# main.net
KiCad netlist of a schematic drawn in EAGLE
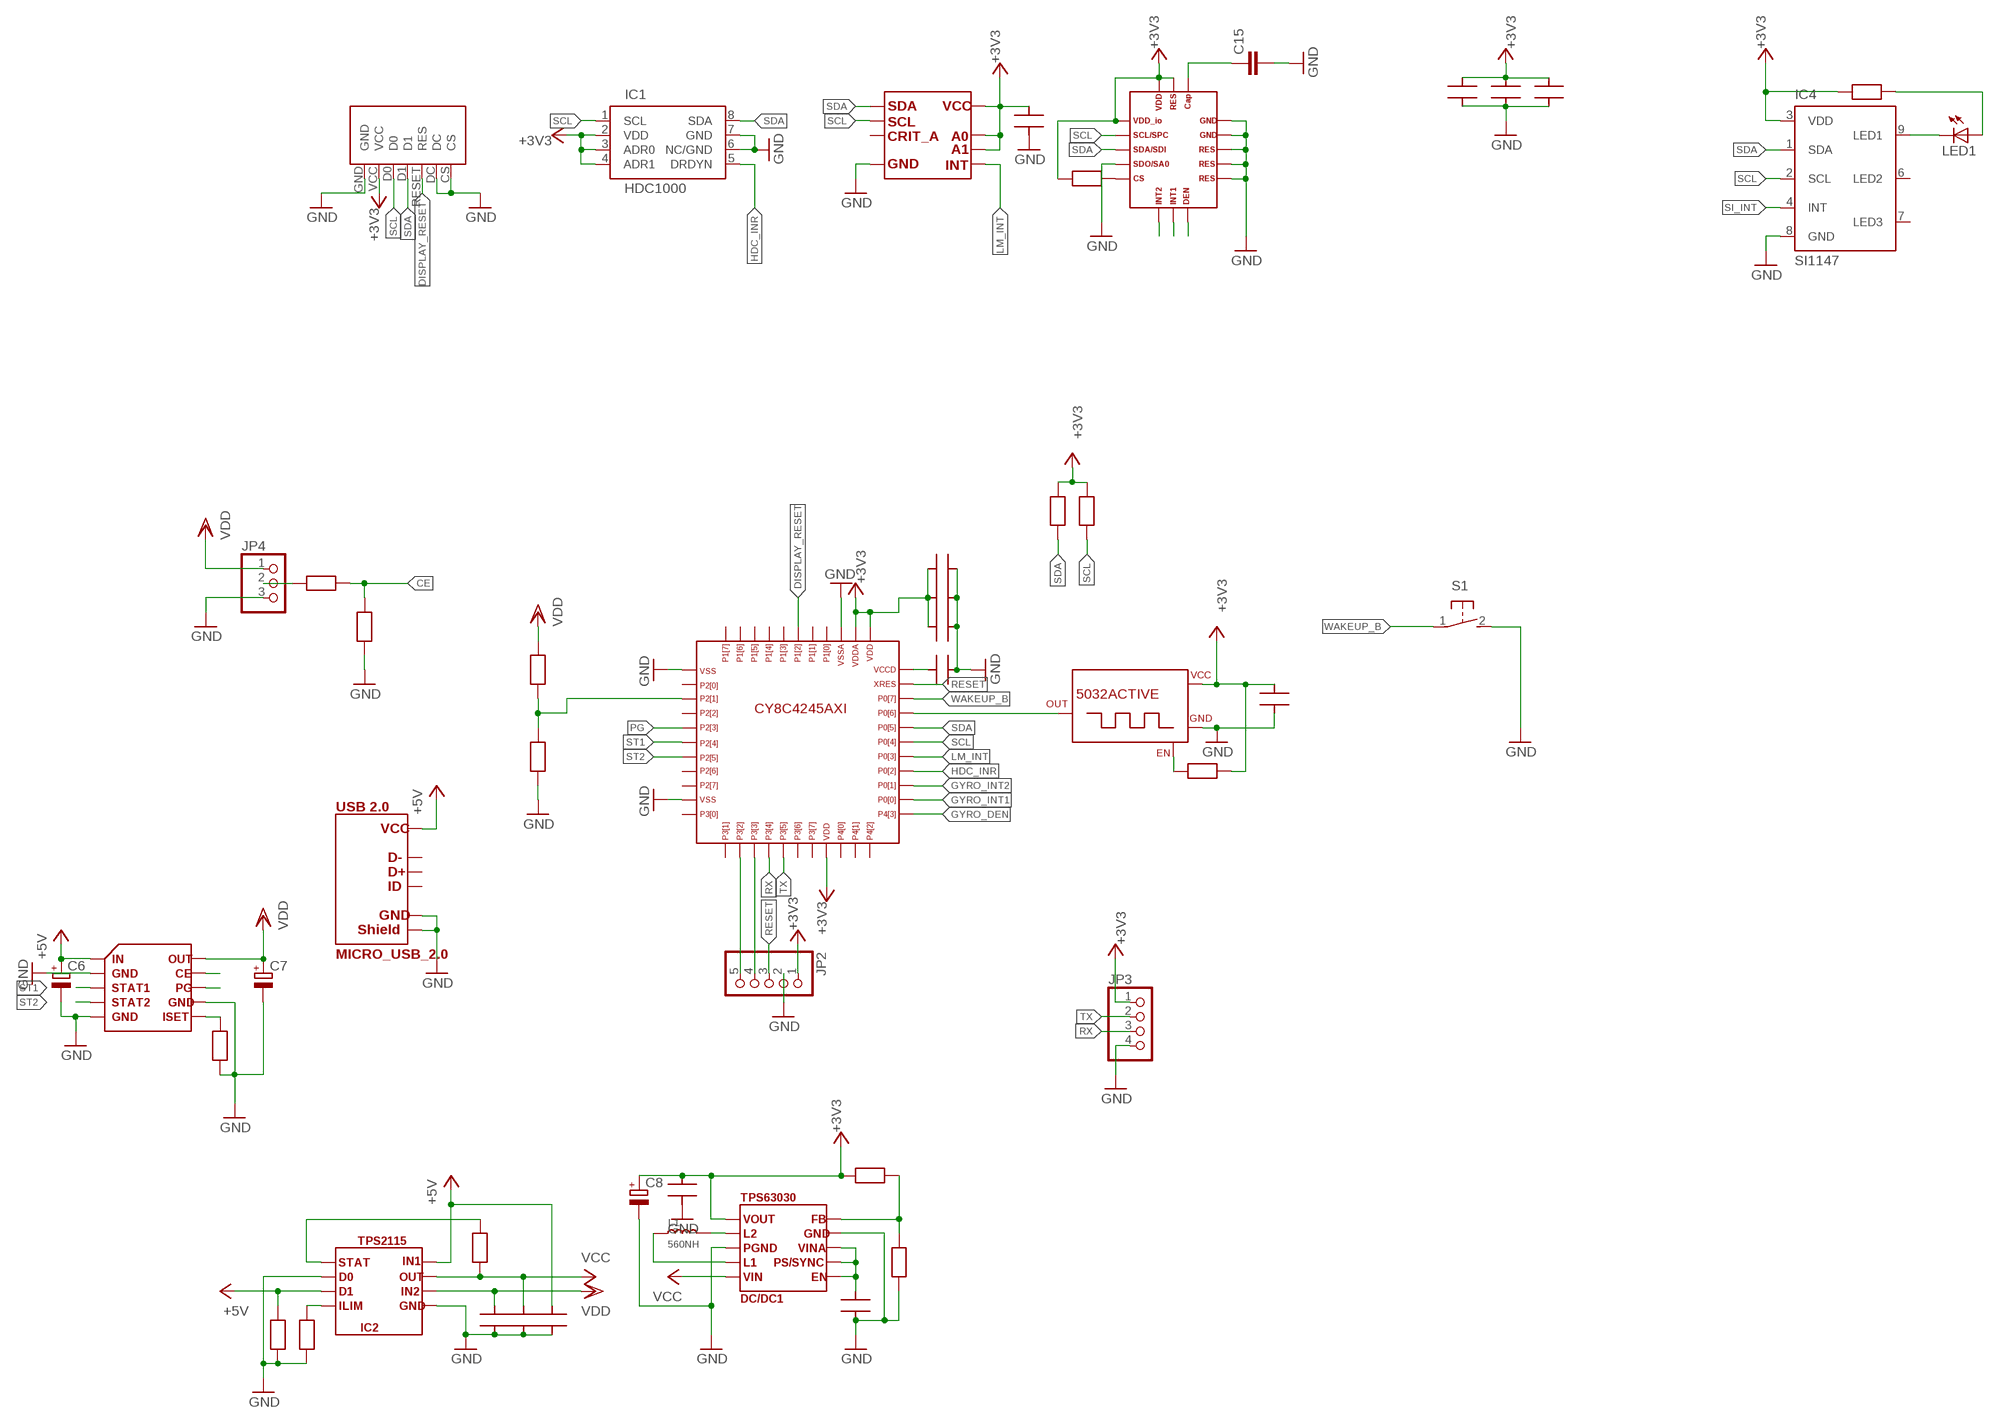
[diagram p0: schematic, sheet 1]

(export (version "E")
  (design (tool "Eeschema 10.0.6"))
  (components
    (comp (ref "C1")
      (value "CAP0603")
      (footprint "eagle-import:C0603")
      (libsource (lib "eagle-import") (part "CAP0603"))
    )
    (comp (ref "C2")
      (value "CAP0603")
      (footprint "eagle-import:C0603")
      (libsource (lib "eagle-import") (part "CAP0603"))
    )
    (comp (ref "C3")
      (value "CAP0603")
      (footprint "eagle-import:C0603")
      (libsource (lib "eagle-import") (part "CAP0603"))
    )
    (comp (ref "C4")
      (value "CAP0603")
      (footprint "eagle-import:C0603")
      (libsource (lib "eagle-import") (part "CAP0603"))
    )
    (comp (ref "C5")
      (value "CAP0603")
      (footprint "eagle-import:C0603")
      (libsource (lib "eagle-import") (part "CAP0603"))
    )
    (comp (ref "C6")
      (value "CPOL-EUSMCA")
      (footprint "eagle-import:SMC_A")
      (libsource (lib "eagle-import") (part "CPOL-EUSMCA"))
    )
    (comp (ref "C7")
      (value "CPOL-EUSMCA")
      (footprint "eagle-import:SMC_A")
      (libsource (lib "eagle-import") (part "CPOL-EUSMCA"))
    )
    (comp (ref "C8")
      (value "CPOL-EUSMCA")
      (footprint "eagle-import:SMC_A")
      (libsource (lib "eagle-import") (part "CPOL-EUSMCA"))
    )
    (comp (ref "C9")
      (value "CAP0603")
      (footprint "eagle-import:C0603")
      (libsource (lib "eagle-import") (part "CAP0603"))
    )
    (comp (ref "C10")
      (value "CAP0603")
      (footprint "eagle-import:C0603")
      (libsource (lib "eagle-import") (part "CAP0603"))
    )
    (comp (ref "C11")
      (value "CAP0603")
      (footprint "eagle-import:C0603")
      (libsource (lib "eagle-import") (part "CAP0603"))
    )
    (comp (ref "C12")
      (value "CAP0603")
      (footprint "eagle-import:C0603")
      (libsource (lib "eagle-import") (part "CAP0603"))
    )
    (comp (ref "C13")
      (value "CAP0603")
      (footprint "eagle-import:C0603")
      (libsource (lib "eagle-import") (part "CAP0603"))
    )
    (comp (ref "C14")
      (value "CAP0603")
      (footprint "eagle-import:C0603")
      (libsource (lib "eagle-import") (part "CAP0603"))
    )
    (comp (ref "C15")
      (value "C-EUC1206")
      (footprint "eagle-import:C1206")
      (libsource (lib "eagle-import") (part "C-EUC1206"))
    )
    (comp (ref "C18")
      (value "CAP0603")
      (footprint "eagle-import:C0603")
      (libsource (lib "eagle-import") (part "CAP0603"))
    )
    (comp (ref "C19")
      (value "CAP0603")
      (footprint "eagle-import:C0603")
      (libsource (lib "eagle-import") (part "CAP0603"))
    )
    (comp (ref "C20")
      (value "CAP0603")
      (footprint "eagle-import:C0603")
      (libsource (lib "eagle-import") (part "CAP0603"))
    )
    (comp (ref "DC/DC1")
      (value "TPS63030")
      (footprint "eagle-import:WSON10")
      (libsource (lib "eagle-import") (part "TPS63030"))
    )
    (comp (ref "DIS1")
      (value "ER-OLED_BREACKOUT")
      (footprint "eagle-import:ER-OLED_BRECKOUT")
      (libsource (lib "eagle-import") (part "ER-OLED_BREACKOUT"))
    )
    (comp (ref "GYRO1")
      (value "L3GD20H")
      (footprint "eagle-import:LGA_3X3_16")
      (libsource (lib "eagle-import") (part "L3GD20H"))
    )
    (comp (ref "IC1")
      (value "HDC1000")
      (footprint "eagle-import:DSBGA-8")
      (libsource (lib "eagle-import") (part "HDC1000"))
    )
    (comp (ref "IC2")
      (value "TPS2115")
      (footprint "eagle-import:TSSOP8")
      (libsource (lib "eagle-import") (part "TPS2115"))
    )
    (comp (ref "IC3")
      (value "BQ24080-Q1,")
      (footprint "eagle-import:VSON10")
      (libsource (lib "eagle-import") (part "BQ24080-Q1,"))
    )
    (comp (ref "IC4")
      (value "SI1147")
      (footprint "eagle-import:QFN-10")
      (libsource (lib "eagle-import") (part "SI1147"))
    )
    (comp (ref "JP2")
      (value "PINHD-1X5")
      (footprint "eagle-import:1X05")
      (libsource (lib "eagle-import") (part "PINHD-1X5"))
    )
    (comp (ref "JP3")
      (value "PINHD-1X4")
      (footprint "eagle-import:1X04")
      (libsource (lib "eagle-import") (part "PINHD-1X4"))
    )
    (comp (ref "JP4")
      (value "PINHD-1X3")
      (footprint "eagle-import:1X03")
      (libsource (lib "eagle-import") (part "PINHD-1X3"))
    )
    (comp (ref "L1")
      (value "560NH")
      (footprint "eagle-import:L0805")
      (libsource (lib "eagle-import") (part "SMD-INDUCTOR-560NH-10%(0805)"))
    )
    (comp (ref "LED1")
      (value "LED3MM")
      (footprint "eagle-import:LED3MM")
      (libsource (lib "eagle-import") (part "LED3MM"))
    )
    (comp (ref "R1")
      (value "RES0603")
      (footprint "eagle-import:R0603")
      (libsource (lib "eagle-import") (part "RES0603"))
    )
    (comp (ref "R2")
      (value "RES0603")
      (footprint "eagle-import:R0603")
      (libsource (lib "eagle-import") (part "RES0603"))
    )
    (comp (ref "R3")
      (value "RES0603")
      (footprint "eagle-import:R0603")
      (libsource (lib "eagle-import") (part "RES0603"))
    )
    (comp (ref "R4")
      (value "RES0603")
      (footprint "eagle-import:R0603")
      (libsource (lib "eagle-import") (part "RES0603"))
    )
    (comp (ref "R5")
      (value "RES0603")
      (footprint "eagle-import:R0603")
      (libsource (lib "eagle-import") (part "RES0603"))
    )
    (comp (ref "R6")
      (value "RES0603")
      (footprint "eagle-import:R0603")
      (libsource (lib "eagle-import") (part "RES0603"))
    )
    (comp (ref "R7")
      (value "RES0603")
      (footprint "eagle-import:R0603")
      (libsource (lib "eagle-import") (part "RES0603"))
    )
    (comp (ref "R8")
      (value "RES0603")
      (footprint "eagle-import:R0603")
      (libsource (lib "eagle-import") (part "RES0603"))
    )
    (comp (ref "R9")
      (value "RES0603")
      (footprint "eagle-import:R0603")
      (libsource (lib "eagle-import") (part "RES0603"))
    )
    (comp (ref "R10")
      (value "RES0603")
      (footprint "eagle-import:R0603")
      (libsource (lib "eagle-import") (part "RES0603"))
    )
    (comp (ref "R11")
      (value "RES0603")
      (footprint "eagle-import:R0603")
      (libsource (lib "eagle-import") (part "RES0603"))
    )
    (comp (ref "R12")
      (value "RES0603")
      (footprint "eagle-import:R0603")
      (libsource (lib "eagle-import") (part "RES0603"))
    )
    (comp (ref "R13")
      (value "RES0603")
      (footprint "eagle-import:R0603")
      (libsource (lib "eagle-import") (part "RES0603"))
    )
    (comp (ref "R14")
      (value "RES0603")
      (footprint "eagle-import:R0603")
      (libsource (lib "eagle-import") (part "RES0603"))
    )
    (comp (ref "R15")
      (value "RES0603")
      (footprint "eagle-import:R0603")
      (libsource (lib "eagle-import") (part "RES0603"))
    )
    (comp (ref "S1")
      (value "31-XX")
      (footprint "eagle-import:B3F-31XX")
      (fields (field (name "MPN") "B3F-3100"))
      (libsource (lib "eagle-import") (part "31-XX"))
    )
    (comp (ref "TMP1")
      (value "LM92")
      (footprint "eagle-import:SOIC8-1.27-5X4MM")
      (libsource (lib "eagle-import") (part "LM92"))
    )
    (comp (ref "U$1")
      (value "CY8C4245")
      (footprint "eagle-import:TQFP44_CY_LOGO")
      (libsource (lib "eagle-import") (part "CY8C4245"))
    )
    (comp (ref "U$2")
      (value "5032ACTIVE")
      (footprint "eagle-import:5030A")
      (libsource (lib "eagle-import") (part "5032ACTIVE"))
    )
    (comp (ref "USB_CON1")
      (value "MICRO_USB_2.0")
      (footprint "eagle-import:MICRO-USB5+4P-SMD-0.65")
      (libsource (lib "eagle-import") (part "MICRO_USB_2.0"))
    )
  )
  (nets
    (net (code "1") (name "+3V3") (class "Default")
      (node (ref "C10") (pin "2") (pinfunction "P$2_2") (pintype "bidirectional"))
      (node (ref "C11") (pin "2") (pinfunction "P$2_2") (pintype "bidirectional"))
      (node (ref "C12") (pin "2") (pinfunction "P$2_2") (pintype "bidirectional"))
      (node (ref "C13") (pin "1") (pinfunction "P$1_1") (pintype "bidirectional"))
      (node (ref "C14") (pin "1") (pinfunction "P$1_1") (pintype "bidirectional"))
      (node (ref "C18") (pin "1") (pinfunction "P$1_1") (pintype "bidirectional"))
      (node (ref "C19") (pin "1") (pinfunction "P$1_1") (pintype "bidirectional"))
      (node (ref "C20") (pin "1") (pinfunction "P$1_1") (pintype "bidirectional"))
      (node (ref "C5") (pin "2") (pinfunction "P$2_2") (pintype "bidirectional"))
      (node (ref "C8") (pin "+") (pinfunction "+_+") (pintype "passive"))
      (node (ref "DC/DC1") (pin "P$1") (pinfunction "P$1_P$1") (pintype "bidirectional"))
      (node (ref "DIS1") (pin "VCC") (pinfunction "VCC_VCC") (pintype "bidirectional"))
      (node (ref "GYRO1") (pin "1") (pinfunction "P$1_1") (pintype "bidirectional"))
      (node (ref "GYRO1") (pin "15") (pinfunction "P$15_15") (pintype "bidirectional"))
      (node (ref "GYRO1") (pin "16") (pinfunction "P$16_16") (pintype "bidirectional"))
      (node (ref "IC1") (pin "2") (pinfunction "VDD_2") (pintype "power_in"))
      (node (ref "IC1") (pin "3") (pinfunction "ADR0_3") (pintype "bidirectional"))
      (node (ref "IC1") (pin "4") (pinfunction "ADR1_4") (pintype "bidirectional"))
      (node (ref "IC4") (pin "3") (pinfunction "VDD_3") (pintype "power_in"))
      (node (ref "JP2") (pin "1") (pinfunction "1_1") (pintype "passive"))
      (node (ref "JP3") (pin "1") (pinfunction "1_1") (pintype "passive"))
      (node (ref "R10") (pin "2") (pinfunction "P$2_2") (pintype "bidirectional"))
      (node (ref "R11") (pin "1") (pinfunction "P$1_1") (pintype "bidirectional"))
      (node (ref "R12") (pin "2") (pinfunction "P$2_2") (pintype "bidirectional"))
      (node (ref "R13") (pin "2") (pinfunction "P$2_2") (pintype "bidirectional"))
      (node (ref "R5") (pin "1") (pinfunction "P$1_1") (pintype "bidirectional"))
      (node (ref "R9") (pin "2") (pinfunction "P$2_2") (pintype "bidirectional"))
      (node (ref "TMP1") (pin "6") (pinfunction "OUT_6") (pintype "bidirectional"))
      (node (ref "TMP1") (pin "7") (pinfunction "OUT_7") (pintype "bidirectional"))
      (node (ref "TMP1") (pin "8") (pinfunction "OUT_8") (pintype "bidirectional"))
      (node (ref "U$1") (pin "19") (pinfunction "19_19") (pintype "bidirectional"))
      (node (ref "U$1") (pin "34") (pinfunction "34_34") (pintype "bidirectional"))
      (node (ref "U$1") (pin "35") (pinfunction "35_35") (pintype "bidirectional"))
      (node (ref "U$2") (pin "4") (pinfunction "+5V_4") (pintype "bidirectional"))
    )
    (net (code "2") (name "+5V") (class "Default")
      (node (ref "C3") (pin "2") (pinfunction "P$2_2") (pintype "bidirectional"))
      (node (ref "C6") (pin "+") (pinfunction "+_+") (pintype "passive"))
      (node (ref "IC2") (pin "P$3") (pinfunction "P$3_P$3") (pintype "bidirectional"))
      (node (ref "IC2") (pin "P$8") (pinfunction "P$8_P$8") (pintype "bidirectional"))
      (node (ref "IC3") (pin "P$1") (pinfunction "P$1_P$1") (pintype "bidirectional"))
      (node (ref "R2") (pin "2") (pinfunction "P$2_2") (pintype "bidirectional"))
      (node (ref "USB_CON1") (pin "1") (pinfunction "P$1_1") (pintype "bidirectional"))
    )
    (net (code "3") (name "CE") (class "Default")
      (node (ref "IC3") (pin "P$9") (pinfunction "P$9_P$9") (pintype "bidirectional"))
      (node (ref "R14") (pin "1") (pinfunction "P$1_1") (pintype "bidirectional"))
      (node (ref "R15") (pin "1") (pinfunction "P$1_1") (pintype "bidirectional"))
    )
    (net (code "4") (name "DISPLAY_RESET") (class "Default")
      (node (ref "DIS1") (pin "RESET") (pinfunction "RES_RESET") (pintype "bidirectional"))
      (node (ref "U$1") (pin "39") (pinfunction "39_39") (pintype "bidirectional"))
    )
    (net (code "5") (name "GND") (class "Default")
      (node (ref "C1") (pin "1") (pinfunction "P$1_1") (pintype "bidirectional"))
      (node (ref "C10") (pin "1") (pinfunction "P$1_1") (pintype "bidirectional"))
      (node (ref "C11") (pin "1") (pinfunction "P$1_1") (pintype "bidirectional"))
      (node (ref "C12") (pin "1") (pinfunction "P$1_1") (pintype "bidirectional"))
      (node (ref "C13") (pin "2") (pinfunction "P$2_2") (pintype "bidirectional"))
      (node (ref "C14") (pin "2") (pinfunction "P$2_2") (pintype "bidirectional"))
      (node (ref "C15") (pin "2") (pinfunction "2_2") (pintype "passive"))
      (node (ref "C18") (pin "2") (pinfunction "P$2_2") (pintype "bidirectional"))
      (node (ref "C19") (pin "2") (pinfunction "P$2_2") (pintype "bidirectional"))
      (node (ref "C2") (pin "1") (pinfunction "P$1_1") (pintype "bidirectional"))
      (node (ref "C20") (pin "2") (pinfunction "P$2_2") (pintype "bidirectional"))
      (node (ref "C3") (pin "1") (pinfunction "P$1_1") (pintype "bidirectional"))
      (node (ref "C4") (pin "1") (pinfunction "P$1_1") (pintype "bidirectional"))
      (node (ref "C5") (pin "1") (pinfunction "P$1_1") (pintype "bidirectional"))
      (node (ref "C6") (pin "-") (pinfunction "-_-") (pintype "passive"))
      (node (ref "C7") (pin "-") (pinfunction "-_-") (pintype "passive"))
      (node (ref "C8") (pin "-") (pinfunction "-_-") (pintype "passive"))
      (node (ref "C9") (pin "1") (pinfunction "P$1_1") (pintype "bidirectional"))
      (node (ref "DC/DC1") (pin "EPAD_B") (pinfunction "P$3_EPAD_B") (pintype "bidirectional"))
      (node (ref "DC/DC1") (pin "EPAD_T") (pinfunction "P$3_EPAD_T") (pintype "bidirectional"))
      (node (ref "DC/DC1") (pin "EPAD_VIA") (pinfunction "P$3_EPAD_VIA") (pintype "bidirectional"))
      (node (ref "DC/DC1") (pin "P$3") (pinfunction "P$3_P$3") (pintype "bidirectional"))
      (node (ref "DC/DC1") (pin "P$9") (pinfunction "P$9_P$9") (pintype "bidirectional"))
      (node (ref "DIS1") (pin "CS") (pinfunction "CS_CS") (pintype "bidirectional"))
      (node (ref "DIS1") (pin "DC") (pinfunction "DC_DC") (pintype "bidirectional"))
      (node (ref "DIS1") (pin "GND") (pinfunction "GND_GND") (pintype "bidirectional"))
      (node (ref "GYRO1") (pin "10") (pinfunction "P$10_10") (pintype "bidirectional"))
      (node (ref "GYRO1") (pin "11") (pinfunction "P$11_11") (pintype "bidirectional"))
      (node (ref "GYRO1") (pin "12") (pinfunction "P$12_12") (pintype "bidirectional"))
      (node (ref "GYRO1") (pin "13") (pinfunction "P$13_13") (pintype "bidirectional"))
      (node (ref "GYRO1") (pin "4") (pinfunction "P$4_4") (pintype "bidirectional"))
      (node (ref "GYRO1") (pin "9") (pinfunction "P$9_9") (pintype "bidirectional"))
      (node (ref "IC1") (pin "6") (pinfunction "NC/GND_6") (pintype "bidirectional"))
      (node (ref "IC1") (pin "7") (pinfunction "GND_7") (pintype "power_in"))
      (node (ref "IC2") (pin "P$2") (pinfunction "P$2_P$2") (pintype "bidirectional"))
      (node (ref "IC2") (pin "P$5") (pinfunction "P$5_P$5") (pintype "bidirectional"))
      (node (ref "IC3") (pin "P$2") (pinfunction "P$2_P$2") (pintype "bidirectional"))
      (node (ref "IC3") (pin "P$5") (pinfunction "P$5_P$5") (pintype "bidirectional"))
      (node (ref "IC3") (pin "P$7") (pinfunction "P$7_P$7") (pintype "bidirectional"))
      (node (ref "IC3") (pin "PAD1") (pinfunction "P$5_PAD1") (pintype "bidirectional"))
      (node (ref "IC3") (pin "PAD2") (pinfunction "P$5_PAD2") (pintype "bidirectional"))
      (node (ref "IC3") (pin "PAD3") (pinfunction "P$5_PAD3") (pintype "bidirectional"))
      (node (ref "IC3") (pin "PAD4") (pinfunction "P$5_PAD4") (pintype "bidirectional"))
      (node (ref "IC3") (pin "PAD5") (pinfunction "P$5_PAD5") (pintype "bidirectional"))
      (node (ref "IC4") (pin "8") (pinfunction "GND_8") (pintype "power_in"))
      (node (ref "JP2") (pin "2") (pinfunction "2_2") (pintype "passive"))
      (node (ref "JP3") (pin "4") (pinfunction "4_4") (pintype "passive"))
      (node (ref "JP4") (pin "3") (pinfunction "3_3") (pintype "passive"))
      (node (ref "R1") (pin "1") (pinfunction "P$1_1") (pintype "bidirectional"))
      (node (ref "R15") (pin "2") (pinfunction "P$2_2") (pintype "bidirectional"))
      (node (ref "R2") (pin "1") (pinfunction "P$1_1") (pintype "bidirectional"))
      (node (ref "R4") (pin "2") (pinfunction "P$2_2") (pintype "bidirectional"))
      (node (ref "R6") (pin "1") (pinfunction "P$1_1") (pintype "bidirectional"))
      (node (ref "R8") (pin "1") (pinfunction "P$1_1") (pintype "bidirectional"))
      (node (ref "S1") (pin "2") (pinfunction "S_2") (pintype "passive"))
      (node (ref "TMP1") (pin "4") (pinfunction "OUT_4") (pintype "bidirectional"))
      (node (ref "U$1") (pin "1") (pinfunction "1_1") (pintype "bidirectional"))
      (node (ref "U$1") (pin "10") (pinfunction "10_10") (pintype "bidirectional"))
      (node (ref "U$1") (pin "36") (pinfunction "36_36") (pintype "bidirectional"))
      (node (ref "U$2") (pin "2") (pinfunction "GND_2") (pintype "bidirectional"))
      (node (ref "USB_CON1") (pin "5") (pinfunction "P$5_5") (pintype "bidirectional"))
      (node (ref "USB_CON1") (pin "P$1") (pinfunction "P$6_P$1") (pintype "bidirectional"))
      (node (ref "USB_CON1") (pin "P$2") (pinfunction "P$6_P$2") (pintype "bidirectional"))
      (node (ref "USB_CON1") (pin "P$3") (pinfunction "P$6_P$3") (pintype "bidirectional"))
      (node (ref "USB_CON1") (pin "P$4") (pinfunction "P$6_P$4") (pintype "bidirectional"))
    )
    (net (code "6") (name "GYRO_DEN") (class "Default")
      (node (ref "GYRO1") (pin "8") (pinfunction "P$8_8") (pintype "bidirectional"))
      (node (ref "U$1") (pin "23") (pinfunction "23_23") (pintype "bidirectional"))
    )
    (net (code "7") (name "GYRO_INT1") (class "Default")
      (node (ref "GYRO1") (pin "7") (pinfunction "P$7_7") (pintype "bidirectional"))
      (node (ref "U$1") (pin "24") (pinfunction "24_24") (pintype "bidirectional"))
    )
    (net (code "8") (name "GYRO_INT2") (class "Default")
      (node (ref "GYRO1") (pin "6") (pinfunction "P$6_6") (pintype "bidirectional"))
      (node (ref "U$1") (pin "25") (pinfunction "25_25") (pintype "bidirectional"))
    )
    (net (code "9") (name "HDC_INR") (class "Default")
      (node (ref "IC1") (pin "5") (pinfunction "DRDYN_5") (pintype "bidirectional"))
      (node (ref "U$1") (pin "26") (pinfunction "26_26") (pintype "bidirectional"))
    )
    (net (code "10") (name "LM_INT") (class "Default")
      (node (ref "TMP1") (pin "5") (pinfunction "OUT_5") (pintype "bidirectional"))
      (node (ref "U$1") (pin "27") (pinfunction "27_27") (pintype "bidirectional"))
    )
    (net (code "11") (name "Net-(C4-P$2)") (class "Default")
      (node (ref "C4") (pin "2") (pinfunction "P$2_2") (pintype "bidirectional"))
      (node (ref "DC/DC1") (pin "P$6") (pinfunction "P$6_P$6") (pintype "bidirectional"))
      (node (ref "DC/DC1") (pin "P$7") (pinfunction "P$7_P$7") (pintype "bidirectional"))
      (node (ref "DC/DC1") (pin "P$8") (pinfunction "P$8_P$8") (pintype "bidirectional"))
    )
    (net (code "12") (name "Net-(C9-P$2)") (class "Default")
      (node (ref "C9") (pin "2") (pinfunction "P$2_2") (pintype "bidirectional"))
      (node (ref "U$1") (pin "33") (pinfunction "33_33") (pintype "bidirectional"))
    )
    (net (code "13") (name "Net-(DC/DC1-PadP$2)") (class "Default")
      (node (ref "DC/DC1") (pin "P$2") (pinfunction "P$2_P$2") (pintype "bidirectional"))
      (node (ref "L1") (pin "2") (pinfunction "2_2") (pintype "passive"))
    )
    (net (code "14") (name "Net-(DC/DC1-PadP$4)") (class "Default")
      (node (ref "DC/DC1") (pin "P$4") (pinfunction "P$4_P$4") (pintype "bidirectional"))
      (node (ref "L1") (pin "1") (pinfunction "1_1") (pintype "passive"))
    )
    (net (code "15") (name "Net-(GYRO1-P$5)") (class "Default")
      (node (ref "GYRO1") (pin "5") (pinfunction "P$5_5") (pintype "bidirectional"))
      (node (ref "R12") (pin "1") (pinfunction "P$1_1") (pintype "bidirectional"))
    )
    (net (code "16") (name "Net-(GYRO1-P$14)") (class "Default")
      (node (ref "C15") (pin "1") (pinfunction "1_1") (pintype "passive"))
      (node (ref "GYRO1") (pin "14") (pinfunction "P$14_14") (pintype "bidirectional"))
    )
    (net (code "17") (name "Net-(IC4-LED1)") (class "Default")
      (node (ref "IC4") (pin "9") (pinfunction "LED1_9") (pintype "output"))
      (node (ref "LED1") (pin "K") (pinfunction "C_K") (pintype "passive"))
    )
    (net (code "18") (name "Net-(JP2-Pad4)") (class "Default")
      (node (ref "JP2") (pin "4") (pinfunction "4_4") (pintype "passive"))
      (node (ref "U$1") (pin "14") (pinfunction "14_14") (pintype "bidirectional"))
    )
    (net (code "19") (name "Net-(JP2-Pad5)") (class "Default")
      (node (ref "JP2") (pin "5") (pinfunction "5_5") (pintype "passive"))
      (node (ref "U$1") (pin "13") (pinfunction "13_13") (pintype "bidirectional"))
    )
    (net (code "20") (name "Net-(R1-P$2)") (class "Default")
      (node (ref "IC2") (pin "P$4") (pinfunction "P$4_P$4") (pintype "bidirectional"))
      (node (ref "R1") (pin "2") (pinfunction "P$2_2") (pintype "bidirectional"))
    )
    (net (code "21") (name "Net-(R3-P$2)") (class "Default")
      (node (ref "IC2") (pin "P$1") (pinfunction "P$1_P$1") (pintype "bidirectional"))
      (node (ref "R3") (pin "2") (pinfunction "P$2_2") (pintype "bidirectional"))
    )
    (net (code "22") (name "Net-(R4-P$1)") (class "Default")
      (node (ref "DC/DC1") (pin "P$10") (pinfunction "P$10_P$10") (pintype "bidirectional"))
      (node (ref "R4") (pin "1") (pinfunction "P$1_1") (pintype "bidirectional"))
      (node (ref "R5") (pin "2") (pinfunction "P$2_2") (pintype "bidirectional"))
    )
    (net (code "23") (name "Net-(R6-P$2)") (class "Default")
      (node (ref "IC3") (pin "P$6") (pinfunction "P$6_P$6") (pintype "bidirectional"))
      (node (ref "R6") (pin "2") (pinfunction "P$2_2") (pintype "bidirectional"))
    )
    (net (code "24") (name "Net-(R7-P$1)") (class "Default")
      (node (ref "R7") (pin "1") (pinfunction "P$1_1") (pintype "bidirectional"))
      (node (ref "R8") (pin "2") (pinfunction "P$2_2") (pintype "bidirectional"))
      (node (ref "U$1") (pin "3") (pinfunction "3_3") (pintype "bidirectional"))
    )
    (net (code "25") (name "Net-(R11-P$2)") (class "Default")
      (node (ref "R11") (pin "2") (pinfunction "P$2_2") (pintype "bidirectional"))
      (node (ref "U$2") (pin "1") (pinfunction "EN_1") (pintype "bidirectional"))
    )
    (net (code "26") (name "Net-(R13-P$1)") (class "Default")
      (node (ref "LED1") (pin "A") (pinfunction "A_A") (pintype "passive"))
      (node (ref "R13") (pin "1") (pinfunction "P$1_1") (pintype "bidirectional"))
    )
    (net (code "27") (name "Net-(R14-P$2)") (class "Default")
      (node (ref "JP4") (pin "2") (pinfunction "2_2") (pintype "passive"))
      (node (ref "R14") (pin "2") (pinfunction "P$2_2") (pintype "bidirectional"))
    )
    (net (code "28") (name "Net-(U$2-OUT)") (class "Default")
      (node (ref "U$1") (pin "30") (pinfunction "30_30") (pintype "bidirectional"))
      (node (ref "U$2") (pin "3") (pinfunction "OUT_3") (pintype "bidirectional"))
    )
    (net (code "29") (name "PG") (class "Default")
      (node (ref "IC3") (pin "P$8") (pinfunction "P$8_P$8") (pintype "bidirectional"))
      (node (ref "U$1") (pin "5") (pinfunction "5_5") (pintype "bidirectional"))
    )
    (net (code "30") (name "RESET") (class "Default")
      (node (ref "JP2") (pin "3") (pinfunction "3_3") (pintype "passive"))
      (node (ref "U$1") (pin "32") (pinfunction "32_32") (pintype "bidirectional"))
    )
    (net (code "31") (name "RX") (class "Default")
      (node (ref "JP3") (pin "3") (pinfunction "3_3") (pintype "passive"))
      (node (ref "U$1") (pin "15") (pinfunction "15_15") (pintype "bidirectional"))
    )
    (net (code "32") (name "SCL") (class "Default")
      (node (ref "DIS1") (pin "D0") (pinfunction "D0_D0") (pintype "bidirectional"))
      (node (ref "GYRO1") (pin "2") (pinfunction "P$2_2") (pintype "bidirectional"))
      (node (ref "IC1") (pin "1") (pinfunction "SCL_1") (pintype "bidirectional"))
      (node (ref "IC4") (pin "2") (pinfunction "SCL_2") (pintype "input"))
      (node (ref "R10") (pin "1") (pinfunction "P$1_1") (pintype "bidirectional"))
      (node (ref "TMP1") (pin "2") (pinfunction "OUT_2") (pintype "bidirectional"))
      (node (ref "U$1") (pin "28") (pinfunction "28_28") (pintype "bidirectional"))
    )
    (net (code "33") (name "SDA") (class "Default")
      (node (ref "DIS1") (pin "D1") (pinfunction "D1_D1") (pintype "bidirectional"))
      (node (ref "GYRO1") (pin "3") (pinfunction "P$3_3") (pintype "bidirectional"))
      (node (ref "IC1") (pin "8") (pinfunction "SDA_8") (pintype "bidirectional"))
      (node (ref "IC4") (pin "1") (pinfunction "SDA_1") (pintype "bidirectional"))
      (node (ref "R9") (pin "1") (pinfunction "P$1_1") (pintype "bidirectional"))
      (node (ref "TMP1") (pin "1") (pinfunction "OUT_1") (pintype "bidirectional"))
      (node (ref "U$1") (pin "29") (pinfunction "29_29") (pintype "bidirectional"))
    )
    (net (code "34") (name "SI_INT") (class "Default")
      (node (ref "IC4") (pin "4") (pinfunction "INT_4") (pintype "open_collector"))
    )
    (net (code "35") (name "ST1") (class "Default")
      (node (ref "IC3") (pin "P$3") (pinfunction "P$3_P$3") (pintype "bidirectional"))
      (node (ref "U$1") (pin "6") (pinfunction "6_6") (pintype "bidirectional"))
    )
    (net (code "36") (name "ST2") (class "Default")
      (node (ref "IC3") (pin "P$4") (pinfunction "P$4_P$4") (pintype "bidirectional"))
      (node (ref "U$1") (pin "7") (pinfunction "7_7") (pintype "bidirectional"))
    )
    (net (code "37") (name "TX") (class "Default")
      (node (ref "JP3") (pin "2") (pinfunction "2_2") (pintype "passive"))
      (node (ref "U$1") (pin "16") (pinfunction "16_16") (pintype "bidirectional"))
    )
    (net (code "38") (name "VCC") (class "Default")
      (node (ref "C2") (pin "2") (pinfunction "P$2_2") (pintype "bidirectional"))
      (node (ref "DC/DC1") (pin "P$5") (pinfunction "P$5_P$5") (pintype "bidirectional"))
      (node (ref "IC2") (pin "P$7") (pinfunction "P$7_P$7") (pintype "bidirectional"))
      (node (ref "R3") (pin "1") (pinfunction "P$1_1") (pintype "bidirectional"))
    )
    (net (code "39") (name "VDD") (class "Default")
      (node (ref "C1") (pin "2") (pinfunction "P$2_2") (pintype "bidirectional"))
      (node (ref "C7") (pin "+") (pinfunction "+_+") (pintype "passive"))
      (node (ref "IC2") (pin "P$6") (pinfunction "P$6_P$6") (pintype "bidirectional"))
      (node (ref "IC3") (pin "P$10") (pinfunction "P$10_P$10") (pintype "bidirectional"))
      (node (ref "JP4") (pin "1") (pinfunction "1_1") (pintype "passive"))
      (node (ref "R7") (pin "2") (pinfunction "P$2_2") (pintype "bidirectional"))
    )
    (net (code "40") (name "WAKEUP_B") (class "Default")
      (node (ref "S1") (pin "1") (pinfunction "P_1") (pintype "passive"))
      (node (ref "U$1") (pin "31") (pinfunction "31_31") (pintype "bidirectional"))
    )
    (net (code "41") (name "unconnected-(IC4-LED2-Pad6)") (class "Default")
      (node (ref "IC4") (pin "6") (pinfunction "LED2_6") (pintype "output"))
    )
    (net (code "42") (name "unconnected-(IC4-LED3-Pad7)") (class "Default")
      (node (ref "IC4") (pin "7") (pinfunction "LED3_7") (pintype "output"))
    )
    (net (code "43") (name "unconnected-(TMP1-OUT-Pad3)") (class "Default")
      (node (ref "TMP1") (pin "3") (pinfunction "OUT_3") (pintype "bidirectional"))
    )
    (net (code "44") (name "unconnected-(U$1-Pad2)") (class "Default")
      (node (ref "U$1") (pin "2") (pinfunction "2_2") (pintype "bidirectional"))
    )
    (net (code "45") (name "unconnected-(U$1-Pad4)") (class "Default")
      (node (ref "U$1") (pin "4") (pinfunction "4_4") (pintype "bidirectional"))
    )
    (net (code "46") (name "unconnected-(U$1-Pad8)") (class "Default")
      (node (ref "U$1") (pin "8") (pinfunction "8_8") (pintype "bidirectional"))
    )
    (net (code "47") (name "unconnected-(U$1-Pad9)") (class "Default")
      (node (ref "U$1") (pin "9") (pinfunction "9_9") (pintype "bidirectional"))
    )
    (net (code "48") (name "unconnected-(U$1-Pad11)") (class "Default")
      (node (ref "U$1") (pin "11") (pinfunction "11_11") (pintype "bidirectional"))
    )
    (net (code "49") (name "unconnected-(U$1-Pad12)") (class "Default")
      (node (ref "U$1") (pin "12") (pinfunction "12_12") (pintype "bidirectional"))
    )
    (net (code "50") (name "unconnected-(U$1-Pad17)") (class "Default")
      (node (ref "U$1") (pin "17") (pinfunction "17_17") (pintype "bidirectional"))
    )
    (net (code "51") (name "unconnected-(U$1-Pad18)") (class "Default")
      (node (ref "U$1") (pin "18") (pinfunction "18_18") (pintype "bidirectional"))
    )
    (net (code "52") (name "unconnected-(U$1-Pad20)") (class "Default")
      (node (ref "U$1") (pin "20") (pinfunction "20_20") (pintype "bidirectional"))
    )
    (net (code "53") (name "unconnected-(U$1-Pad21)") (class "Default")
      (node (ref "U$1") (pin "21") (pinfunction "21_21") (pintype "bidirectional"))
    )
    (net (code "54") (name "unconnected-(U$1-Pad22)") (class "Default")
      (node (ref "U$1") (pin "22") (pinfunction "22_22") (pintype "bidirectional"))
    )
    (net (code "55") (name "unconnected-(U$1-Pad37)") (class "Default")
      (node (ref "U$1") (pin "37") (pinfunction "37_37") (pintype "bidirectional"))
    )
    (net (code "56") (name "unconnected-(U$1-Pad38)") (class "Default")
      (node (ref "U$1") (pin "38") (pinfunction "38_38") (pintype "bidirectional"))
    )
    (net (code "57") (name "unconnected-(U$1-Pad40)") (class "Default")
      (node (ref "U$1") (pin "40") (pinfunction "40_40") (pintype "bidirectional"))
    )
    (net (code "58") (name "unconnected-(U$1-Pad41)") (class "Default")
      (node (ref "U$1") (pin "41") (pinfunction "41_41") (pintype "bidirectional"))
    )
    (net (code "59") (name "unconnected-(U$1-Pad42)") (class "Default")
      (node (ref "U$1") (pin "42") (pinfunction "42_42") (pintype "bidirectional"))
    )
    (net (code "60") (name "unconnected-(U$1-Pad43)") (class "Default")
      (node (ref "U$1") (pin "43") (pinfunction "43_43") (pintype "bidirectional"))
    )
    (net (code "61") (name "unconnected-(U$1-Pad44)") (class "Default")
      (node (ref "U$1") (pin "44") (pinfunction "44_44") (pintype "bidirectional"))
    )
    (net (code "62") (name "unconnected-(USB_CON1-P$2-Pad2)") (class "Default")
      (node (ref "USB_CON1") (pin "2") (pinfunction "P$2_2") (pintype "bidirectional"))
    )
    (net (code "63") (name "unconnected-(USB_CON1-P$3-Pad3)") (class "Default")
      (node (ref "USB_CON1") (pin "3") (pinfunction "P$3_3") (pintype "bidirectional"))
    )
    (net (code "64") (name "unconnected-(USB_CON1-P$4-Pad4)") (class "Default")
      (node (ref "USB_CON1") (pin "4") (pinfunction "P$4_4") (pintype "bidirectional"))
    )
  )
)
